# mMicroSD.net
KiCad netlist of a schematic drawn in EAGLE
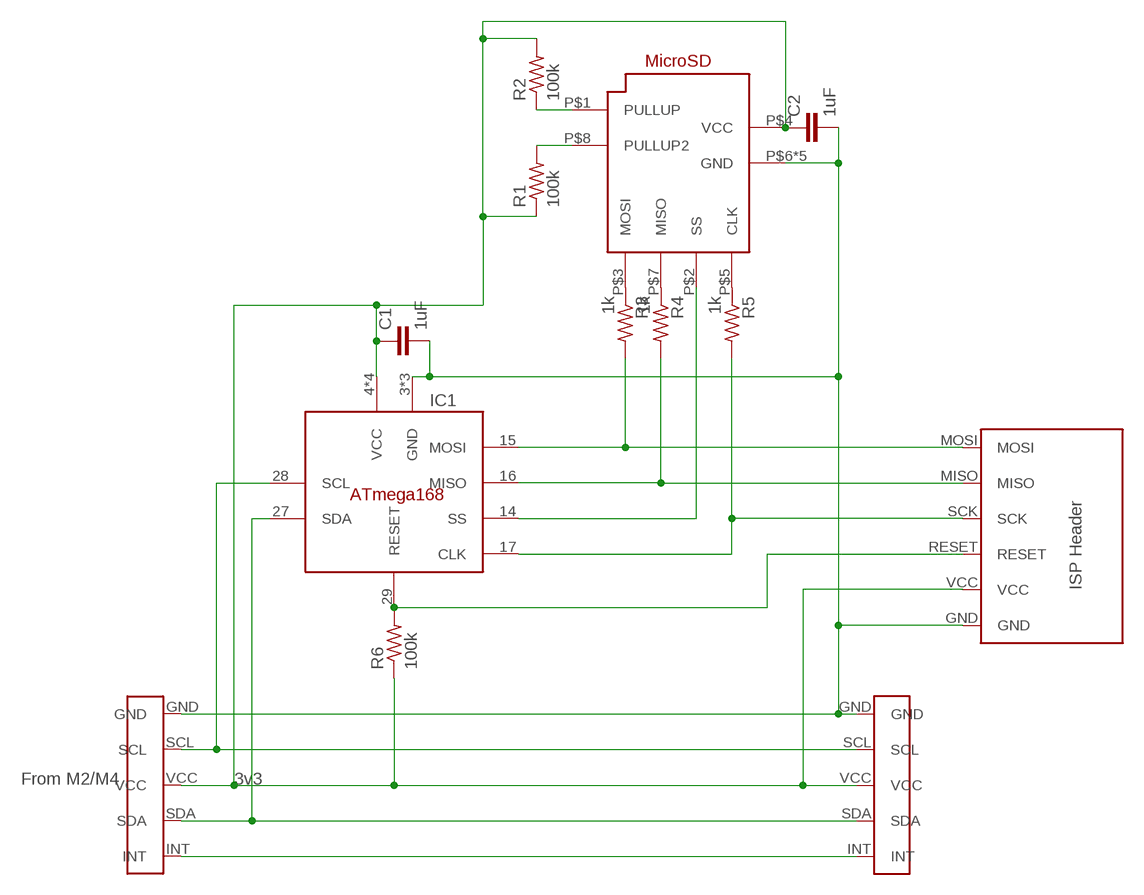
[diagram p0: schematic, sheet 1]

(export (version "E")
  (design (tool "Eeschema 10.0.6"))
  (components
    (comp (ref "C1")
      (value "1uF")
      (footprint "eagle-import:C0805")
      (libsource (lib "eagle-import") (part "C-EUC0805"))
    )
    (comp (ref "C2")
      (value "1uF")
      (footprint "eagle-import:C0805")
      (libsource (lib "eagle-import") (part "C-EUC0805"))
    )
    (comp (ref "IC1")
      (value "ATMEGA168")
      (footprint "eagle-import:ATMEGA168")
      (libsource (lib "eagle-import") (part "ATMEGA168"))
    )
    (comp (ref "R1")
      (value "100k")
      (footprint "eagle-import:R2012")
      (libsource (lib "eagle-import") (part "R-US_R2012"))
    )
    (comp (ref "R2")
      (value "100k")
      (footprint "eagle-import:R2012")
      (libsource (lib "eagle-import") (part "R-US_R2012"))
    )
    (comp (ref "R3")
      (value "1k")
      (footprint "eagle-import:R2012")
      (libsource (lib "eagle-import") (part "R-US_R2012"))
    )
    (comp (ref "R4")
      (value "1k")
      (footprint "eagle-import:R2012")
      (libsource (lib "eagle-import") (part "R-US_R2012"))
    )
    (comp (ref "R5")
      (value "1k")
      (footprint "eagle-import:R2012")
      (libsource (lib "eagle-import") (part "R-US_R2012"))
    )
    (comp (ref "R6")
      (value "100k")
      (footprint "eagle-import:R2012")
      (libsource (lib "eagle-import") (part "R-US_R2012"))
    )
    (comp (ref "SDCONN")
      (value "101-00660-68-6")
      (footprint "eagle-import:101-00660-68-6")
      (libsource (lib "eagle-import") (part "101-00660-68-6"))
    )
    (comp (ref "U$1")
      (value "MBUS_OUT")
      (footprint "eagle-import:MBUS_OUT")
      (libsource (lib "eagle-import") (part "MBUS_OUT"))
    )
    (comp (ref "U$2")
      (value "MBUS_IN")
      (footprint "eagle-import:MBUS_IN")
      (libsource (lib "eagle-import") (part "MBUS_IN"))
    )
    (comp (ref "U$3")
      (value "ISP")
      (footprint "eagle-import:ISP")
      (libsource (lib "eagle-import") (part "ISP"))
    )
  )
  (nets
    (net (code "1") (name "Net-(C1-Pad2)") (class "Default")
      (node (ref "C1") (pin "2") (pinfunction "2_2") (pintype "passive"))
      (node (ref "C2") (pin "2") (pinfunction "2_2") (pintype "passive"))
      (node (ref "IC1") (pin "21") (pinfunction "GND_21") (pintype "bidirectional"))
      (node (ref "IC1") (pin "3") (pinfunction "GND_3") (pintype "bidirectional"))
      (node (ref "IC1") (pin "5") (pinfunction "GND_5") (pintype "bidirectional"))
      (node (ref "SDCONN") (pin "P$10") (pinfunction "GND_P$10") (pintype "bidirectional"))
      (node (ref "SDCONN") (pin "P$11") (pinfunction "GND_P$11") (pintype "bidirectional"))
      (node (ref "SDCONN") (pin "P$12") (pinfunction "GND_P$12") (pintype "bidirectional"))
      (node (ref "SDCONN") (pin "P$6") (pinfunction "GND_P$6") (pintype "bidirectional"))
      (node (ref "SDCONN") (pin "P$9") (pinfunction "GND_P$9") (pintype "bidirectional"))
      (node (ref "U$1") (pin "GND") (pinfunction "GND_GND") (pintype "bidirectional"))
      (node (ref "U$2") (pin "GND") (pinfunction "GND_GND") (pintype "bidirectional"))
      (node (ref "U$3") (pin "GND") (pinfunction "GND_GND") (pintype "bidirectional"))
    )
    (net (code "2") (name "Net-(IC1-CLK)") (class "Default")
      (node (ref "IC1") (pin "17") (pinfunction "CLK_17") (pintype "bidirectional"))
      (node (ref "R5") (pin "2") (pinfunction "2_2") (pintype "passive"))
      (node (ref "U$3") (pin "SCK") (pinfunction "SCK_SCK") (pintype "bidirectional"))
    )
    (net (code "3") (name "Net-(IC1-MISO)") (class "Default")
      (node (ref "IC1") (pin "16") (pinfunction "MISO_16") (pintype "bidirectional"))
      (node (ref "R4") (pin "2") (pinfunction "2_2") (pintype "passive"))
      (node (ref "U$3") (pin "MISO") (pinfunction "MISO_MISO") (pintype "bidirectional"))
    )
    (net (code "4") (name "Net-(IC1-MOSI)") (class "Default")
      (node (ref "IC1") (pin "15") (pinfunction "MOSI_15") (pintype "bidirectional"))
      (node (ref "R3") (pin "2") (pinfunction "2_2") (pintype "passive"))
      (node (ref "U$3") (pin "MOSI") (pinfunction "MOSI_MOSI") (pintype "bidirectional"))
    )
    (net (code "5") (name "Net-(IC1-RESET)") (class "Default")
      (node (ref "IC1") (pin "29") (pinfunction "RESET_29") (pintype "bidirectional"))
      (node (ref "R6") (pin "2") (pinfunction "2_2") (pintype "passive"))
      (node (ref "U$3") (pin "RESET") (pinfunction "RESET_RESET") (pintype "bidirectional"))
    )
    (net (code "6") (name "Net-(IC1-SCL)") (class "Default")
      (node (ref "IC1") (pin "28") (pinfunction "SCL_28") (pintype "bidirectional"))
      (node (ref "U$1") (pin "SCL") (pinfunction "SCL_SCL") (pintype "bidirectional"))
      (node (ref "U$2") (pin "SCL") (pinfunction "SCL_SCL") (pintype "bidirectional"))
    )
    (net (code "7") (name "Net-(IC1-SDA)") (class "Default")
      (node (ref "IC1") (pin "27") (pinfunction "SDA_27") (pintype "bidirectional"))
      (node (ref "U$1") (pin "SDA") (pinfunction "SDA_SDA") (pintype "bidirectional"))
      (node (ref "U$2") (pin "SDA") (pinfunction "SDA_SDA") (pintype "bidirectional"))
    )
    (net (code "8") (name "Net-(IC1-SS)") (class "Default")
      (node (ref "IC1") (pin "14") (pinfunction "SS_14") (pintype "bidirectional"))
      (node (ref "SDCONN") (pin "P$2") (pinfunction "SS_P$2") (pintype "bidirectional"))
    )
    (net (code "9") (name "Net-(SDCONN-CLK)") (class "Default")
      (node (ref "R5") (pin "1") (pinfunction "1_1") (pintype "passive"))
      (node (ref "SDCONN") (pin "P$5") (pinfunction "CLK_P$5") (pintype "bidirectional"))
    )
    (net (code "10") (name "Net-(SDCONN-MISO)") (class "Default")
      (node (ref "R4") (pin "1") (pinfunction "1_1") (pintype "passive"))
      (node (ref "SDCONN") (pin "P$7") (pinfunction "MISO_P$7") (pintype "bidirectional"))
    )
    (net (code "11") (name "Net-(SDCONN-MOSI)") (class "Default")
      (node (ref "R3") (pin "1") (pinfunction "1_1") (pintype "passive"))
      (node (ref "SDCONN") (pin "P$3") (pinfunction "MOSI_P$3") (pintype "bidirectional"))
    )
    (net (code "12") (name "Net-(SDCONN-PULLUP)") (class "Default")
      (node (ref "R2") (pin "1") (pinfunction "1_1") (pintype "passive"))
      (node (ref "SDCONN") (pin "P$1") (pinfunction "PULLUP_P$1") (pintype "bidirectional"))
    )
    (net (code "13") (name "Net-(SDCONN-PULLUP2)") (class "Default")
      (node (ref "R1") (pin "2") (pinfunction "2_2") (pintype "passive"))
      (node (ref "SDCONN") (pin "P$8") (pinfunction "PULLUP2_P$8") (pintype "bidirectional"))
    )
    (net (code "14") (name "Net-(SDCONN-VCC)") (class "Default")
      (node (ref "C1") (pin "1") (pinfunction "1_1") (pintype "passive"))
      (node (ref "C2") (pin "1") (pinfunction "1_1") (pintype "passive"))
      (node (ref "IC1") (pin "18") (pinfunction "VCC_18") (pintype "bidirectional"))
      (node (ref "IC1") (pin "20") (pinfunction "VCC_20") (pintype "bidirectional"))
      (node (ref "IC1") (pin "4") (pinfunction "VCC_4") (pintype "bidirectional"))
      (node (ref "IC1") (pin "6") (pinfunction "VCC_6") (pintype "bidirectional"))
      (node (ref "R1") (pin "1") (pinfunction "1_1") (pintype "passive"))
      (node (ref "R2") (pin "2") (pinfunction "2_2") (pintype "passive"))
      (node (ref "R6") (pin "1") (pinfunction "1_1") (pintype "passive"))
      (node (ref "SDCONN") (pin "P$4") (pinfunction "VCC_P$4") (pintype "bidirectional"))
      (node (ref "U$1") (pin "VCC") (pinfunction "VCC_VCC") (pintype "bidirectional"))
      (node (ref "U$2") (pin "VCC") (pinfunction "VCC_VCC") (pintype "bidirectional"))
      (node (ref "U$3") (pin "VCC") (pinfunction "VCC_VCC") (pintype "bidirectional"))
    )
    (net (code "15") (name "Net-(U$1-PadINT)") (class "Default")
      (node (ref "U$1") (pin "INT") (pinfunction "INT_INT") (pintype "bidirectional"))
      (node (ref "U$2") (pin "INT") (pinfunction "INT_INT") (pintype "bidirectional"))
    )
  )
)
